# zasilanie.net
KiCad netlist of a schematic drawn in EAGLE
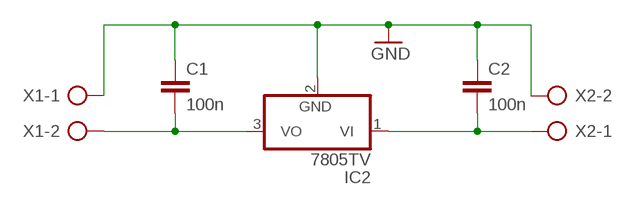
[diagram p0: schematic, sheet 1]

(export (version "E")
  (design (tool "Eeschema 10.0.6"))
  (components
    (comp (ref "C1")
      (value "100n")
      (footprint "eagle-import:C0805")
      (libsource (lib "eagle-import") (part "C-EUC0805"))
    )
    (comp (ref "C2")
      (value "100n")
      (footprint "eagle-import:C0805")
      (libsource (lib "eagle-import") (part "C-EUC0805"))
    )
    (comp (ref "IC2")
      (value "7805TV")
      (footprint "eagle-import:TO220V")
      (libsource (lib "eagle-import") (part "78TV05"))
    )
    (comp (ref "X1")
      (value "AK500/2-H")
      (footprint "eagle-import:AK500_2-H")
      (libsource (lib "eagle-import") (part "AK500/2-H"))
    )
    (comp (ref "X2")
      (value "AK500/2-H")
      (footprint "eagle-import:AK500_2-H")
      (libsource (lib "eagle-import") (part "AK500/2-H"))
    )
  )
  (nets
    (net (code "1") (name "GND") (class "Default")
      (node (ref "C1") (pin "1") (pinfunction "1_1") (pintype "passive"))
      (node (ref "C2") (pin "1") (pinfunction "1_1") (pintype "passive"))
      (node (ref "IC2") (pin "2") (pinfunction "GND_2") (pintype "passive"))
      (node (ref "X1") (pin "1") (pinfunction "KL_1") (pintype "passive"))
      (node (ref "X2") (pin "2") (pinfunction "KL_2") (pintype "passive"))
    )
    (net (code "2") (name "Net-(IC2-VI)") (class "Default")
      (node (ref "C2") (pin "2") (pinfunction "2_2") (pintype "passive"))
      (node (ref "IC2") (pin "1") (pinfunction "VI_1") (pintype "input"))
      (node (ref "X2") (pin "1") (pinfunction "KL_1") (pintype "passive"))
    )
    (net (code "3") (name "Net-(IC2-VO)") (class "Default")
      (node (ref "C1") (pin "2") (pinfunction "2_2") (pintype "passive"))
      (node (ref "IC2") (pin "3") (pinfunction "VO_3") (pintype "passive"))
      (node (ref "X1") (pin "2") (pinfunction "KL_2") (pintype "passive"))
    )
  )
)
